# geiger2.net
KiCad netlist of a schematic drawn in EAGLE
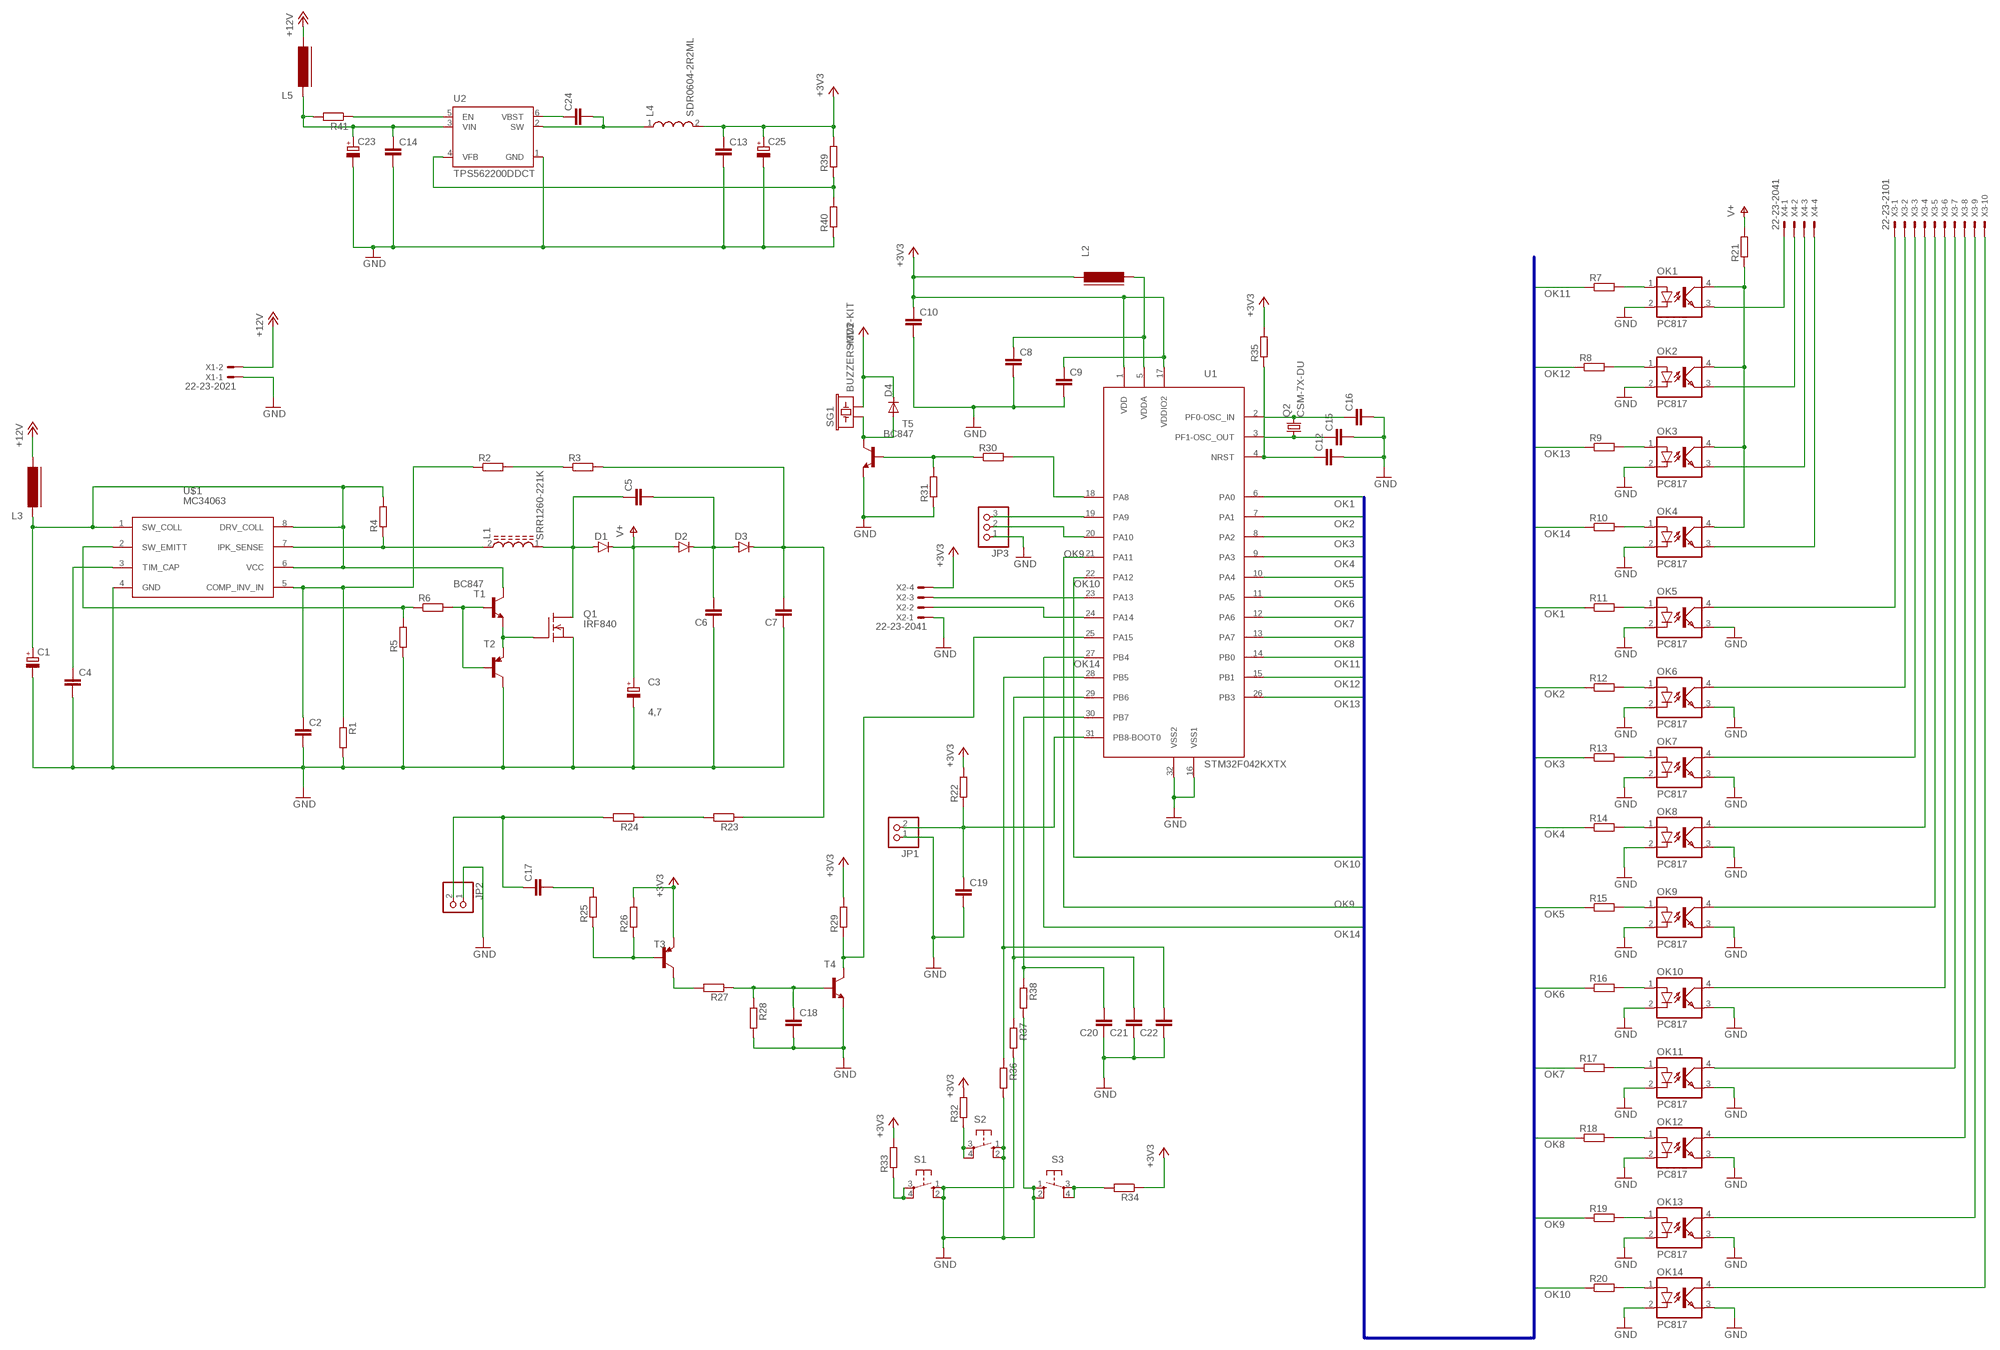
[diagram p0: schematic, sheet 1]

(export (version "E")
  (design (tool "Eeschema 10.0.6"))
  (components
    (comp (ref "C1")
      (value "CPOL-EUCT7343")
      (footprint "eagle-import:CT7343")
      (libsource (lib "eagle-import") (part "CPOL-EUCT7343"))
    )
    (comp (ref "C2")
      (value "C-EUC0805")
      (footprint "eagle-import:C0805")
      (libsource (lib "eagle-import") (part "rcl_334_C-EUC0805"))
    )
    (comp (ref "C3")
      (value "4,7")
      (footprint "eagle-import:E5-10,5")
      (libsource (lib "eagle-import") (part "rcl_334_CPOL-EUE5-10.5"))
    )
    (comp (ref "C4")
      (value "C-EUC0805")
      (footprint "eagle-import:C0805")
      (libsource (lib "eagle-import") (part "rcl_334_C-EUC0805"))
    )
    (comp (ref "C5")
      (value "C-EUC1812K")
      (footprint "eagle-import:C1812K")
      (libsource (lib "eagle-import") (part "C-EUC1812K"))
    )
    (comp (ref "C6")
      (value "C-EUC1812K")
      (footprint "eagle-import:C1812K")
      (libsource (lib "eagle-import") (part "C-EUC1812K"))
    )
    (comp (ref "C7")
      (value "C-EUC1812K")
      (footprint "eagle-import:C1812K")
      (libsource (lib "eagle-import") (part "C-EUC1812K"))
    )
    (comp (ref "C8")
      (value "C-EUC0805")
      (footprint "eagle-import:C0805")
      (libsource (lib "eagle-import") (part "rcl_334_C-EUC0805"))
    )
    (comp (ref "C9")
      (value "C-EUC0805")
      (footprint "eagle-import:C0805")
      (libsource (lib "eagle-import") (part "rcl_334_C-EUC0805"))
    )
    (comp (ref "C10")
      (value "C-EUC0805")
      (footprint "eagle-import:C0805")
      (libsource (lib "eagle-import") (part "rcl_334_C-EUC0805"))
    )
    (comp (ref "C12")
      (value "C-EUC0805")
      (footprint "eagle-import:C0805")
      (libsource (lib "eagle-import") (part "rcl_334_C-EUC0805"))
    )
    (comp (ref "C13")
      (value "C-EUC0805")
      (footprint "eagle-import:C0805")
      (libsource (lib "eagle-import") (part "rcl_334_C-EUC0805"))
    )
    (comp (ref "C14")
      (value "C-EUC0805")
      (footprint "eagle-import:C0805")
      (libsource (lib "eagle-import") (part "rcl_334_C-EUC0805"))
    )
    (comp (ref "C15")
      (value "C-EUC0805")
      (footprint "eagle-import:C0805")
      (libsource (lib "eagle-import") (part "rcl_334_C-EUC0805"))
    )
    (comp (ref "C16")
      (value "C-EUC0805")
      (footprint "eagle-import:C0805")
      (libsource (lib "eagle-import") (part "rcl_334_C-EUC0805"))
    )
    (comp (ref "C17")
      (value "C-EUC1206K")
      (footprint "eagle-import:C1206K")
      (libsource (lib "eagle-import") (part "rcl_334_C-EUC1206K"))
    )
    (comp (ref "C18")
      (value "C-EUC0805K")
      (footprint "eagle-import:C0805K")
      (libsource (lib "eagle-import") (part "rcl_334_C-EUC0805K"))
    )
    (comp (ref "C19")
      (value "C-EUC0805K")
      (footprint "eagle-import:C0805K")
      (libsource (lib "eagle-import") (part "rcl_334_C-EUC0805K"))
    )
    (comp (ref "C20")
      (value "C-EUC0805K")
      (footprint "eagle-import:C0805K")
      (libsource (lib "eagle-import") (part "rcl_334_C-EUC0805K"))
    )
    (comp (ref "C21")
      (value "C-EUC0805K")
      (footprint "eagle-import:C0805K")
      (libsource (lib "eagle-import") (part "rcl_334_C-EUC0805K"))
    )
    (comp (ref "C22")
      (value "C-EUC0805K")
      (footprint "eagle-import:C0805K")
      (libsource (lib "eagle-import") (part "rcl_334_C-EUC0805K"))
    )
    (comp (ref "C23")
      (value "CPOL-EUCT7343")
      (footprint "eagle-import:CT7343")
      (libsource (lib "eagle-import") (part "CPOL-EUCT7343"))
    )
    (comp (ref "C24")
      (value "C-EUC0805")
      (footprint "eagle-import:C0805")
      (libsource (lib "eagle-import") (part "rcl_334_C-EUC0805"))
    )
    (comp (ref "C25")
      (value "CPOL-EUCT7343")
      (footprint "eagle-import:CT7343")
      (libsource (lib "eagle-import") (part "CPOL-EUCT7343"))
    )
    (comp (ref "D1")
      (value "DIODE-DO214AC")
      (footprint "eagle-import:DO214AC")
      (libsource (lib "eagle-import") (part "DIODE-DO214AC"))
    )
    (comp (ref "D2")
      (value "DIODE-DO214AC")
      (footprint "eagle-import:DO214AC")
      (libsource (lib "eagle-import") (part "DIODE-DO214AC"))
    )
    (comp (ref "D3")
      (value "DIODE-DO214AC")
      (footprint "eagle-import:DO214AC")
      (libsource (lib "eagle-import") (part "DIODE-DO214AC"))
    )
    (comp (ref "D4")
      (value "DIODE-SOD-123")
      (footprint "eagle-import:SOD-123")
      (libsource (lib "eagle-import") (part "DIODE-SOD-123"))
    )
    (comp (ref "JP1")
      (value "PINHD-1X2")
      (footprint "eagle-import:1X02")
      (libsource (lib "eagle-import") (part "PINHD-1X2"))
    )
    (comp (ref "JP2")
      (value "PINHD-1X2")
      (footprint "eagle-import:1X02")
      (libsource (lib "eagle-import") (part "PINHD-1X2"))
    )
    (comp (ref "JP3")
      (value "PINHD-1X3")
      (footprint "eagle-import:1X03")
      (libsource (lib "eagle-import") (part "PINHD-1X3"))
    )
    (comp (ref "L1")
      (value "SRR1260-221K")
      (footprint "eagle-import:INDP125125X600N")
      (fields (field (name "MF") "Bourns - J.W. Miller"))
      (libsource (lib "eagle-import") (part "SRR1260-221K"))
    )
    (comp (ref "L2")
      (value "FERRITE-0805")
      (footprint "eagle-import:FB805")
      (libsource (lib "eagle-import") (part "FERRITE-0805"))
    )
    (comp (ref "L3")
      (value "FERRITE-0805")
      (footprint "eagle-import:FB805")
      (libsource (lib "eagle-import") (part "FERRITE-0805"))
    )
    (comp (ref "L4")
      (value "SDR0604-2R2ML")
      (footprint "eagle-import:INDP5858X480N")
      (fields (field (name "MF") "Bourns"))
      (libsource (lib "eagle-import") (part "SDR0604-2R2ML"))
    )
    (comp (ref "L5")
      (value "FERRITE-0805")
      (footprint "eagle-import:FB805")
      (libsource (lib "eagle-import") (part "FERRITE-0805"))
    )
    (comp (ref "OK1")
      (value "PC817")
      (footprint "eagle-import:DIL04")
      (fields (field (name "MPN") "PC817X4J000F"))
      (libsource (lib "eagle-import") (part "PC817"))
    )
    (comp (ref "OK2")
      (value "PC817")
      (footprint "eagle-import:DIL04")
      (fields (field (name "MPN") "PC817X4J000F"))
      (libsource (lib "eagle-import") (part "PC817"))
    )
    (comp (ref "OK3")
      (value "PC817")
      (footprint "eagle-import:DIL04")
      (fields (field (name "MPN") "PC817X4J000F"))
      (libsource (lib "eagle-import") (part "PC817"))
    )
    (comp (ref "OK4")
      (value "PC817")
      (footprint "eagle-import:DIL04")
      (fields (field (name "MPN") "PC817X4J000F"))
      (libsource (lib "eagle-import") (part "PC817"))
    )
    (comp (ref "OK5")
      (value "PC817")
      (footprint "eagle-import:DIL04")
      (fields (field (name "MPN") "PC817X4J000F"))
      (libsource (lib "eagle-import") (part "PC817"))
    )
    (comp (ref "OK6")
      (value "PC817")
      (footprint "eagle-import:DIL04")
      (fields (field (name "MPN") "PC817X4J000F"))
      (libsource (lib "eagle-import") (part "PC817"))
    )
    (comp (ref "OK7")
      (value "PC817")
      (footprint "eagle-import:DIL04")
      (fields (field (name "MPN") "PC817X4J000F"))
      (libsource (lib "eagle-import") (part "PC817"))
    )
    (comp (ref "OK8")
      (value "PC817")
      (footprint "eagle-import:DIL04")
      (fields (field (name "MPN") "PC817X4J000F"))
      (libsource (lib "eagle-import") (part "PC817"))
    )
    (comp (ref "OK9")
      (value "PC817")
      (footprint "eagle-import:DIL04")
      (fields (field (name "MPN") "PC817X4J000F"))
      (libsource (lib "eagle-import") (part "PC817"))
    )
    (comp (ref "OK10")
      (value "PC817")
      (footprint "eagle-import:DIL04")
      (fields (field (name "MPN") "PC817X4J000F"))
      (libsource (lib "eagle-import") (part "PC817"))
    )
    (comp (ref "OK11")
      (value "PC817")
      (footprint "eagle-import:DIL04")
      (fields (field (name "MPN") "PC817X4J000F"))
      (libsource (lib "eagle-import") (part "PC817"))
    )
    (comp (ref "OK12")
      (value "PC817")
      (footprint "eagle-import:DIL04")
      (fields (field (name "MPN") "PC817X4J000F"))
      (libsource (lib "eagle-import") (part "PC817"))
    )
    (comp (ref "OK13")
      (value "PC817")
      (footprint "eagle-import:DIL04")
      (fields (field (name "MPN") "PC817X4J000F"))
      (libsource (lib "eagle-import") (part "PC817"))
    )
    (comp (ref "OK14")
      (value "PC817")
      (footprint "eagle-import:DIL04")
      (fields (field (name "MPN") "PC817X4J000F"))
      (libsource (lib "eagle-import") (part "PC817"))
    )
    (comp (ref "Q1")
      (value "IRF840")
      (footprint "eagle-import:TO220")
      (libsource (lib "eagle-import") (part "IRF840"))
    )
    (comp (ref "Q2")
      (value "CSM-7X-DU")
      (footprint "eagle-import:CSM-7X-DU")
      (libsource (lib "eagle-import") (part "CSM-7X-DU"))
    )
    (comp (ref "R1")
      (value "R-EU_R0805")
      (footprint "eagle-import:R0805")
      (libsource (lib "eagle-import") (part "R-EU_R0805"))
    )
    (comp (ref "R2")
      (value "R-EU_R0805")
      (footprint "eagle-import:R0805")
      (libsource (lib "eagle-import") (part "R-EU_R0805"))
    )
    (comp (ref "R3")
      (value "R-EU_R0805")
      (footprint "eagle-import:R0805")
      (libsource (lib "eagle-import") (part "R-EU_R0805"))
    )
    (comp (ref "R4")
      (value "R-EU_R2512")
      (footprint "eagle-import:R2512")
      (libsource (lib "eagle-import") (part "R-EU_R2512"))
    )
    (comp (ref "R5")
      (value "R-EU_R0805")
      (footprint "eagle-import:R0805")
      (libsource (lib "eagle-import") (part "R-EU_R0805"))
    )
    (comp (ref "R6")
      (value "R-EU_R0805")
      (footprint "eagle-import:R0805")
      (libsource (lib "eagle-import") (part "R-EU_R0805"))
    )
    (comp (ref "R7")
      (value "R-EU_R0805")
      (footprint "eagle-import:R0805")
      (libsource (lib "eagle-import") (part "R-EU_R0805"))
    )
    (comp (ref "R8")
      (value "R-EU_R0805")
      (footprint "eagle-import:R0805")
      (libsource (lib "eagle-import") (part "R-EU_R0805"))
    )
    (comp (ref "R9")
      (value "R-EU_R0805")
      (footprint "eagle-import:R0805")
      (libsource (lib "eagle-import") (part "R-EU_R0805"))
    )
    (comp (ref "R10")
      (value "R-EU_R0805")
      (footprint "eagle-import:R0805")
      (libsource (lib "eagle-import") (part "R-EU_R0805"))
    )
    (comp (ref "R11")
      (value "R-EU_R0805")
      (footprint "eagle-import:R0805")
      (libsource (lib "eagle-import") (part "R-EU_R0805"))
    )
    (comp (ref "R12")
      (value "R-EU_R0805")
      (footprint "eagle-import:R0805")
      (libsource (lib "eagle-import") (part "R-EU_R0805"))
    )
    (comp (ref "R13")
      (value "R-EU_R0805")
      (footprint "eagle-import:R0805")
      (libsource (lib "eagle-import") (part "R-EU_R0805"))
    )
    (comp (ref "R14")
      (value "R-EU_R0805")
      (footprint "eagle-import:R0805")
      (libsource (lib "eagle-import") (part "R-EU_R0805"))
    )
    (comp (ref "R15")
      (value "R-EU_R0805")
      (footprint "eagle-import:R0805")
      (libsource (lib "eagle-import") (part "R-EU_R0805"))
    )
    (comp (ref "R16")
      (value "R-EU_R0805")
      (footprint "eagle-import:R0805")
      (libsource (lib "eagle-import") (part "R-EU_R0805"))
    )
    (comp (ref "R17")
      (value "R-EU_R0805")
      (footprint "eagle-import:R0805")
      (libsource (lib "eagle-import") (part "R-EU_R0805"))
    )
    (comp (ref "R18")
      (value "R-EU_R0805")
      (footprint "eagle-import:R0805")
      (libsource (lib "eagle-import") (part "R-EU_R0805"))
    )
    (comp (ref "R19")
      (value "R-EU_R0805")
      (footprint "eagle-import:R0805")
      (libsource (lib "eagle-import") (part "R-EU_R0805"))
    )
    (comp (ref "R20")
      (value "R-EU_R0805")
      (footprint "eagle-import:R0805")
      (libsource (lib "eagle-import") (part "R-EU_R0805"))
    )
    (comp (ref "R21")
      (value "R-EU_R1206")
      (footprint "eagle-import:R1206")
      (libsource (lib "eagle-import") (part "R-EU_R1206"))
    )
    (comp (ref "R22")
      (value "R-EU_R0805")
      (footprint "eagle-import:R0805")
      (libsource (lib "eagle-import") (part "R-EU_R0805"))
    )
    (comp (ref "R23")
      (value "R-EU_R1206")
      (footprint "eagle-import:R1206")
      (libsource (lib "eagle-import") (part "R-EU_R1206"))
    )
    (comp (ref "R24")
      (value "R-EU_R1206")
      (footprint "eagle-import:R1206")
      (libsource (lib "eagle-import") (part "R-EU_R1206"))
    )
    (comp (ref "R25")
      (value "R-EU_R0805")
      (footprint "eagle-import:R0805")
      (libsource (lib "eagle-import") (part "R-EU_R0805"))
    )
    (comp (ref "R26")
      (value "R-EU_R0805")
      (footprint "eagle-import:R0805")
      (libsource (lib "eagle-import") (part "R-EU_R0805"))
    )
    (comp (ref "R27")
      (value "R-EU_R0805")
      (footprint "eagle-import:R0805")
      (libsource (lib "eagle-import") (part "R-EU_R0805"))
    )
    (comp (ref "R28")
      (value "R-EU_R0805")
      (footprint "eagle-import:R0805")
      (libsource (lib "eagle-import") (part "R-EU_R0805"))
    )
    (comp (ref "R29")
      (value "R-EU_R0805")
      (footprint "eagle-import:R0805")
      (libsource (lib "eagle-import") (part "R-EU_R0805"))
    )
    (comp (ref "R30")
      (value "R-EU_R0805")
      (footprint "eagle-import:R0805")
      (libsource (lib "eagle-import") (part "R-EU_R0805"))
    )
    (comp (ref "R31")
      (value "R-EU_R0805")
      (footprint "eagle-import:R0805")
      (libsource (lib "eagle-import") (part "R-EU_R0805"))
    )
    (comp (ref "R32")
      (value "R-EU_R0805")
      (footprint "eagle-import:R0805")
      (libsource (lib "eagle-import") (part "R-EU_R0805"))
    )
    (comp (ref "R33")
      (value "R-EU_R0805")
      (footprint "eagle-import:R0805")
      (libsource (lib "eagle-import") (part "R-EU_R0805"))
    )
    (comp (ref "R34")
      (value "R-EU_R0805")
      (footprint "eagle-import:R0805")
      (libsource (lib "eagle-import") (part "R-EU_R0805"))
    )
    (comp (ref "R35")
      (value "R-EU_R0805")
      (footprint "eagle-import:R0805")
      (libsource (lib "eagle-import") (part "R-EU_R0805"))
    )
    (comp (ref "R36")
      (value "R-EU_R0805")
      (footprint "eagle-import:R0805")
      (libsource (lib "eagle-import") (part "R-EU_R0805"))
    )
    (comp (ref "R37")
      (value "R-EU_R0805")
      (footprint "eagle-import:R0805")
      (libsource (lib "eagle-import") (part "R-EU_R0805"))
    )
    (comp (ref "R38")
      (value "R-EU_R0805")
      (footprint "eagle-import:R0805")
      (libsource (lib "eagle-import") (part "R-EU_R0805"))
    )
    (comp (ref "R39")
      (value "R-EU_R0805")
      (footprint "eagle-import:R0805")
      (libsource (lib "eagle-import") (part "R-EU_R0805"))
    )
    (comp (ref "R40")
      (value "R-EU_R0805")
      (footprint "eagle-import:R0805")
      (libsource (lib "eagle-import") (part "R-EU_R0805"))
    )
    (comp (ref "R41")
      (value "R-EU_R0805")
      (footprint "eagle-import:R0805")
      (libsource (lib "eagle-import") (part "R-EU_R0805"))
    )
    (comp (ref "S1")
      (value "10-XX")
      (footprint "eagle-import:B3F-10XX")
      (fields (field (name "MPN") "B3F-1000"))
      (libsource (lib "eagle-import") (part "10-XX"))
    )
    (comp (ref "S2")
      (value "10-XX")
      (footprint "eagle-import:B3F-10XX")
      (fields (field (name "MPN") "B3F-1000"))
      (libsource (lib "eagle-import") (part "10-XX"))
    )
    (comp (ref "S3")
      (value "10-XX")
      (footprint "eagle-import:B3F-10XX")
      (fields (field (name "MPN") "B3F-1000"))
      (libsource (lib "eagle-import") (part "10-XX"))
    )
    (comp (ref "SG1")
      (value "BUZZERSMD2-KIT")
      (footprint "eagle-import:BUZZER-CCV-KIT")
      (libsource (lib "eagle-import") (part "BUZZERSMD2-KIT"))
    )
    (comp (ref "T1")
      (value "BC847")
      (footprint "eagle-import:SOT23")
      (libsource (lib "eagle-import") (part "BC847SMDBLT1"))
    )
    (comp (ref "T2")
      (value "BC857C-PNP-SOT23-BEC")
      (footprint "eagle-import:SOT23-BEC")
      (libsource (lib "eagle-import") (part "transistor-neu-to92_-PNP-SOT23-BECBC857C"))
    )
    (comp (ref "T3")
      (value "BC857A-PNP-SOT23-BEC")
      (footprint "eagle-import:SOT23-BEC")
      (libsource (lib "eagle-import") (part "-PNP-SOT23-BECBC857A"))
    )
    (comp (ref "T4")
      (value "BC847-NPN-SOT23-BEC")
      (footprint "eagle-import:SOT23-BEC")
      (libsource (lib "eagle-import") (part "-NPN-SOT23-BECBC847"))
    )
    (comp (ref "T5")
      (value "BC847")
      (footprint "eagle-import:SOT23")
      (libsource (lib "eagle-import") (part "BC847"))
    )
    (comp (ref "U$1")
      (value "MC34063")
      (footprint "eagle-import:SO-8")
      (libsource (lib "eagle-import") (part "MC34063/MC33063"))
    )
    (comp (ref "U1")
      (value "STM32F042KXTX")
      (footprint "eagle-import:LQFP32")
      (libsource (lib "eagle-import") (part "STM32F042KXTX"))
    )
    (comp (ref "U2")
      (value "TPS562200DDCT")
      (footprint "eagle-import:SOT95P280X110-6N")
      (fields (field (name "MF") "Texas Instruments"))
      (libsource (lib "eagle-import") (part "TPS562200DDCT"))
    )
    (comp (ref "X1")
      (value "22-23-2021")
      (footprint "eagle-import:22-23-2021")
      (fields (field (name "MF") "MOLEX"))
      (libsource (lib "eagle-import") (part "22-23-2021"))
    )
    (comp (ref "X2")
      (value "22-23-2041")
      (footprint "eagle-import:22-23-2041")
      (fields (field (name "MF") "MOLEX"))
      (libsource (lib "eagle-import") (part "22-23-2041"))
    )
    (comp (ref "X3")
      (value "22-23-2101")
      (footprint "eagle-import:22-23-2101")
      (fields (field (name "MF") "MOLEX"))
      (libsource (lib "eagle-import") (part "22-23-2101"))
    )
    (comp (ref "X4")
      (value "22-23-2041")
      (footprint "eagle-import:22-23-2041")
      (fields (field (name "MF") "MOLEX"))
      (libsource (lib "eagle-import") (part "22-23-2041"))
    )
  )
  (nets
    (net (code "1") (name "+3V3") (class "Default")
      (node (ref "C10") (pin "1") (pinfunction "1_1") (pintype "passive"))
      (node (ref "C13") (pin "1") (pinfunction "1_1") (pintype "passive"))
      (node (ref "C25") (pin "+") (pinfunction "+_+") (pintype "passive"))
      (node (ref "C9") (pin "1") (pinfunction "1_1") (pintype "passive"))
      (node (ref "D4") (pin "C") (pinfunction "C_C") (pintype "passive"))
      (node (ref "L2") (pin "1") (pinfunction "1_1") (pintype "passive"))
      (node (ref "L4") (pin "2") (pinfunction "2_2") (pintype "passive"))
      (node (ref "R22") (pin "2") (pinfunction "2_2") (pintype "passive"))
      (node (ref "R26") (pin "2") (pinfunction "2_2") (pintype "passive"))
      (node (ref "R29") (pin "2") (pinfunction "2_2") (pintype "passive"))
      (node (ref "R32") (pin "2") (pinfunction "2_2") (pintype "passive"))
      (node (ref "R33") (pin "2") (pinfunction "2_2") (pintype "passive"))
      (node (ref "R34") (pin "1") (pinfunction "1_1") (pintype "passive"))
      (node (ref "R35") (pin "2") (pinfunction "2_2") (pintype "passive"))
      (node (ref "R39") (pin "2") (pinfunction "2_2") (pintype "passive"))
      (node (ref "SG1") (pin "-") (pinfunction "2_-") (pintype "passive"))
      (node (ref "T3") (pin "E") (pinfunction "E_E") (pintype "passive"))
      (node (ref "U1") (pin "1") (pinfunction "VDD_1") (pintype "bidirectional"))
      (node (ref "U1") (pin "17") (pinfunction "VDDIO2_17") (pintype "bidirectional"))
      (node (ref "X2") (pin "4") (pinfunction "S_4") (pintype "passive"))
    )
    (net (code "2") (name "+12V") (class "Default")
      (node (ref "L3") (pin "2") (pinfunction "2_2") (pintype "passive"))
      (node (ref "L5") (pin "2") (pinfunction "2_2") (pintype "passive"))
      (node (ref "X1") (pin "2") (pinfunction "S_2") (pintype "passive"))
    )
    (net (code "3") (name "/OK1") (class "Default")
      (node (ref "R11") (pin "1") (pinfunction "1_1") (pintype "passive"))
      (node (ref "U1") (pin "6") (pinfunction "PA0_6") (pintype "bidirectional"))
    )
    (net (code "4") (name "/OK2") (class "Default")
      (node (ref "R12") (pin "1") (pinfunction "1_1") (pintype "passive"))
      (node (ref "U1") (pin "7") (pinfunction "PA1_7") (pintype "bidirectional"))
    )
    (net (code "5") (name "/OK3") (class "Default")
      (node (ref "R13") (pin "1") (pinfunction "1_1") (pintype "passive"))
      (node (ref "U1") (pin "8") (pinfunction "PA2_8") (pintype "bidirectional"))
    )
    (net (code "6") (name "/OK4") (class "Default")
      (node (ref "R14") (pin "1") (pinfunction "1_1") (pintype "passive"))
      (node (ref "U1") (pin "9") (pinfunction "PA3_9") (pintype "bidirectional"))
    )
    (net (code "7") (name "/OK5") (class "Default")
      (node (ref "R15") (pin "1") (pinfunction "1_1") (pintype "passive"))
      (node (ref "U1") (pin "10") (pinfunction "PA4_10") (pintype "bidirectional"))
    )
    (net (code "8") (name "/OK6") (class "Default")
      (node (ref "R16") (pin "1") (pinfunction "1_1") (pintype "passive"))
      (node (ref "U1") (pin "11") (pinfunction "PA5_11") (pintype "bidirectional"))
    )
    (net (code "9") (name "/OK7") (class "Default")
      (node (ref "R17") (pin "1") (pinfunction "1_1") (pintype "passive"))
      (node (ref "U1") (pin "12") (pinfunction "PA6_12") (pintype "bidirectional"))
    )
    (net (code "10") (name "/OK8") (class "Default")
      (node (ref "R18") (pin "1") (pinfunction "1_1") (pintype "passive"))
      (node (ref "U1") (pin "13") (pinfunction "PA7_13") (pintype "bidirectional"))
    )
    (net (code "11") (name "/OK9") (class "Default")
      (node (ref "R19") (pin "1") (pinfunction "1_1") (pintype "passive"))
      (node (ref "U1") (pin "21") (pinfunction "PA11_21") (pintype "bidirectional"))
    )
    (net (code "12") (name "/OK10") (class "Default")
      (node (ref "R20") (pin "1") (pinfunction "1_1") (pintype "passive"))
      (node (ref "U1") (pin "22") (pinfunction "PA12_22") (pintype "bidirectional"))
    )
    (net (code "13") (name "/OK11") (class "Default")
      (node (ref "R7") (pin "1") (pinfunction "1_1") (pintype "passive"))
      (node (ref "U1") (pin "14") (pinfunction "PB0_14") (pintype "bidirectional"))
    )
    (net (code "14") (name "/OK12") (class "Default")
      (node (ref "R8") (pin "1") (pinfunction "1_1") (pintype "passive"))
      (node (ref "U1") (pin "15") (pinfunction "PB1_15") (pintype "bidirectional"))
    )
    (net (code "15") (name "/OK13") (class "Default")
      (node (ref "R9") (pin "1") (pinfunction "1_1") (pintype "passive"))
      (node (ref "U1") (pin "26") (pinfunction "PB3_26") (pintype "bidirectional"))
    )
    (net (code "16") (name "/OK14") (class "Default")
      (node (ref "R10") (pin "1") (pinfunction "1_1") (pintype "passive"))
      (node (ref "U1") (pin "27") (pinfunction "PB4_27") (pintype "bidirectional"))
    )
    (net (code "17") (name "GND") (class "Default")
      (node (ref "C1") (pin "-") (pinfunction "-_-") (pintype "passive"))
      (node (ref "C10") (pin "2") (pinfunction "2_2") (pintype "passive"))
      (node (ref "C12") (pin "2") (pinfunction "2_2") (pintype "passive"))
      (node (ref "C13") (pin "2") (pinfunction "2_2") (pintype "passive"))
      (node (ref "C14") (pin "2") (pinfunction "2_2") (pintype "passive"))
      (node (ref "C15") (pin "2") (pinfunction "2_2") (pintype "passive"))
      (node (ref "C16") (pin "2") (pinfunction "2_2") (pintype "passive"))
      (node (ref "C18") (pin "2") (pinfunction "2_2") (pintype "passive"))
      (node (ref "C19") (pin "2") (pinfunction "2_2") (pintype "passive"))
      (node (ref "C2") (pin "2") (pinfunction "2_2") (pintype "passive"))
      (node (ref "C20") (pin "1") (pinfunction "1_1") (pintype "passive"))
      (node (ref "C21") (pin "1") (pinfunction "1_1") (pintype "passive"))
      (node (ref "C22") (pin "1") (pinfunction "1_1") (pintype "passive"))
      (node (ref "C23") (pin "-") (pinfunction "-_-") (pintype "passive"))
      (node (ref "C25") (pin "-") (pinfunction "-_-") (pintype "passive"))
      (node (ref "C3") (pin "-") (pinfunction "-_-") (pintype "passive"))
      (node (ref "C4") (pin "2") (pinfunction "2_2") (pintype "passive"))
      (node (ref "C6") (pin "1") (pinfunction "1_1") (pintype "passive"))
      (node (ref "C7") (pin "1") (pinfunction "1_1") (pintype "passive"))
      (node (ref "C8") (pin "2") (pinfunction "2_2") (pintype "passive"))
      (node (ref "C9") (pin "2") (pinfunction "2_2") (pintype "passive"))
      (node (ref "JP1") (pin "1") (pinfunction "1_1") (pintype "passive"))
      (node (ref "JP2") (pin "1") (pinfunction "1_1") (pintype "passive"))
      (node (ref "JP3") (pin "1") (pinfunction "1_1") (pintype "passive"))
      (node (ref "OK1") (pin "2") (pinfunction "C_2") (pintype "passive"))
      (node (ref "OK10") (pin "2") (pinfunction "C_2") (pintype "passive"))
      (node (ref "OK10") (pin "3") (pinfunction "EMIT_3") (pintype "passive"))
      (node (ref "OK11") (pin "2") (pinfunction "C_2") (pintype "passive"))
      (node (ref "OK11") (pin "3") (pinfunction "EMIT_3") (pintype "passive"))
      (node (ref "OK12") (pin "2") (pinfunction "C_2") (pintype "passive"))
      (node (ref "OK12") (pin "3") (pinfunction "EMIT_3") (pintype "passive"))
      (node (ref "OK13") (pin "2") (pinfunction "C_2") (pintype "passive"))
      (node (ref "OK13") (pin "3") (pinfunction "EMIT_3") (pintype "passive"))
      (node (ref "OK14") (pin "2") (pinfunction "C_2") (pintype "passive"))
      (node (ref "OK14") (pin "3") (pinfunction "EMIT_3") (pintype "passive"))
      (node (ref "OK2") (pin "2") (pinfunction "C_2") (pintype "passive"))
      (node (ref "OK3") (pin "2") (pinfunction "C_2") (pintype "passive"))
      (node (ref "OK4") (pin "2") (pinfunction "C_2") (pintype "passive"))
      (node (ref "OK5") (pin "2") (pinfunction "C_2") (pintype "passive"))
      (node (ref "OK5") (pin "3") (pinfunction "EMIT_3") (pintype "passive"))
      (node (ref "OK6") (pin "2") (pinfunction "C_2") (pintype "passive"))
      (node (ref "OK6") (pin "3") (pinfunction "EMIT_3") (pintype "passive"))
      (node (ref "OK7") (pin "2") (pinfunction "C_2") (pintype "passive"))
      (node (ref "OK7") (pin "3") (pinfunction "EMIT_3") (pintype "passive"))
      (node (ref "OK8") (pin "2") (pinfunction "C_2") (pintype "passive"))
      (node (ref "OK8") (pin "3") (pinfunction "EMIT_3") (pintype "passive"))
      (node (ref "OK9") (pin "2") (pinfunction "C_2") (pintype "passive"))
      (node (ref "OK9") (pin "3") (pinfunction "EMIT_3") (pintype "passive"))
      (node (ref "Q1") (pin "3") (pinfunction "S_3") (pintype "passive"))
      (node (ref "R1") (pin "2") (pinfunction "2_2") (pintype "passive"))
      (node (ref "R28") (pin "2") (pinfunction "2_2") (pintype "passive"))
      (node (ref "R31") (pin "1") (pinfunction "1_1") (pintype "passive"))
      (node (ref "R36") (pin "2") (pinfunction "2_2") (pintype "passive"))
      (node (ref "R37") (pin "2") (pinfunction "2_2") (pintype "passive"))
      (node (ref "R38") (pin "2") (pinfunction "2_2") (pintype "passive"))
      (node (ref "R40") (pin "1") (pinfunction "1_1") (pintype "passive"))
      (node (ref "R5") (pin "1") (pinfunction "1_1") (pintype "passive"))
      (node (ref "S1") (pin "1") (pinfunction "S_1") (pintype "passive"))
      (node (ref "S1") (pin "2") (pinfunction "S1_2") (pintype "passive"))
      (node (ref "S2") (pin "1") (pinfunction "S_1") (pintype "passive"))
      (node (ref "S2") (pin "2") (pinfunction "S1_2") (pintype "passive"))
      (node (ref "S3") (pin "1") (pinfunction "S_1") (pintype "passive"))
      (node (ref "S3") (pin "2") (pinfunction "S1_2") (pintype "passive"))
      (node (ref "T2") (pin "C") (pinfunction "C_C") (pintype "passive"))
      (node (ref "T4") (pin "E") (pinfunction "E_E") (pintype "passive"))
      (node (ref "T5") (pin "2") (pinfunction "E_2") (pintype "passive"))
      (node (ref "U$1") (pin "4") (pinfunction "GND_4") (pintype "bidirectional"))
      (node (ref "U1") (pin "16") (pinfunction "VSS1_16") (pintype "bidirectional"))
      (node (ref "U1") (pin "32") (pinfunction "VSS2_32") (pintype "bidirectional"))
      (node (ref "U2") (pin "1") (pinfunction "GND_1") (pintype "power_in"))
      (node (ref "X1") (pin "1") (pinfunction "S_1") (pintype "passive"))
      (node (ref "X2") (pin "1") (pinfunction "S_1") (pintype "passive"))
    )
    (net (code "18") (name "Net-(C5-Pad2)") (class "Default")
      (node (ref "C5") (pin "2") (pinfunction "2_2") (pintype "passive"))
      (node (ref "C6") (pin "2") (pinfunction "2_2") (pintype "passive"))
      (node (ref "D2") (pin "C") (pinfunction "C_C") (pintype "passive"))
      (node (ref "D3") (pin "A") (pinfunction "A_A") (pintype "passive"))
    )
    (net (code "19") (name "Net-(C7-Pad2)") (class "Default")
      (node (ref "C7") (pin "2") (pinfunction "2_2") (pintype "passive"))
      (node (ref "D3") (pin "C") (pinfunction "C_C") (pintype "passive"))
      (node (ref "R23") (pin "1") (pinfunction "1_1") (pintype "passive"))
      (node (ref "R3") (pin "2") (pinfunction "2_2") (pintype "passive"))
    )
    (net (code "20") (name "Net-(C17-Pad1)") (class "Default")
      (node (ref "C17") (pin "1") (pinfunction "1_1") (pintype "passive"))
      (node (ref "JP2") (pin "2") (pinfunction "2_2") (pintype "passive"))
      (node (ref "R24") (pin "2") (pinfunction "2_2") (pintype "passive"))
    )
    (net (code "21") (name "Net-(C17-Pad2)") (class "Default")
      (node (ref "C17") (pin "2") (pinfunction "2_2") (pintype "passive"))
      (node (ref "R25") (pin "2") (pinfunction "2_2") (pintype "passive"))
    )
    (net (code "22") (name "Net-(C18-Pad1)") (class "Default")
      (node (ref "C18") (pin "1") (pinfunction "1_1") (pintype "passive"))
      (node (ref "R27") (pin "1") (pinfunction "1_1") (pintype "passive"))
      (node (ref "R28") (pin "1") (pinfunction "1_1") (pintype "passive"))
      (node (ref "T4") (pin "B") (pinfunction "B_B") (pintype "passive"))
    )
    (net (code "23") (name "Net-(OK1-A)") (class "Default")
      (node (ref "OK1") (pin "1") (pinfunction "A_1") (pintype "passive"))
      (node (ref "R7") (pin "2") (pinfunction "2_2") (pintype "passive"))
    )
    (net (code "24") (name "Net-(OK1-COL)") (class "Default")
      (node (ref "OK1") (pin "4") (pinfunction "COL_4") (pintype "passive"))
      (node (ref "OK2") (pin "4") (pinfunction "COL_4") (pintype "passive"))
      (node (ref "OK3") (pin "4") (pinfunction "COL_4") (pintype "passive"))
      (node (ref "OK4") (pin "4") (pinfunction "COL_4") (pintype "passive"))
      (node (ref "R21") (pin "1") (pinfunction "1_1") (pintype "passive"))
    )
    (net (code "25") (name "Net-(OK1-EMIT)") (class "Default")
      (node (ref "OK1") (pin "3") (pinfunction "EMIT_3") (pintype "passive"))
      (node (ref "X4") (pin "1") (pinfunction "S_1") (pintype "passive"))
    )
    (net (code "26") (name "Net-(OK2-A)") (class "Default")
      (node (ref "OK2") (pin "1") (pinfunction "A_1") (pintype "passive"))
      (node (ref "R8") (pin "2") (pinfunction "2_2") (pintype "passive"))
    )
    (net (code "27") (name "Net-(OK2-EMIT)") (class "Default")
      (node (ref "OK2") (pin "3") (pinfunction "EMIT_3") (pintype "passive"))
      (node (ref "X4") (pin "2") (pinfunction "S_2") (pintype "passive"))
    )
    (net (code "28") (name "Net-(OK3-A)") (class "Default")
      (node (ref "OK3") (pin "1") (pinfunction "A_1") (pintype "passive"))
      (node (ref "R9") (pin "2") (pinfunction "2_2") (pintype "passive"))
    )
    (net (code "29") (name "Net-(OK3-EMIT)") (class "Default")
      (node (ref "OK3") (pin "3") (pinfunction "EMIT_3") (pintype "passive"))
      (node (ref "X4") (pin "3") (pinfunction "S_3") (pintype "passive"))
    )
    (net (code "30") (name "Net-(OK4-A)") (class "Default")
      (node (ref "OK4") (pin "1") (pinfunction "A_1") (pintype "passive"))
      (node (ref "R10") (pin "2") (pinfunction "2_2") (pintype "passive"))
    )
    (net (code "31") (name "Net-(OK4-EMIT)") (class "Default")
      (node (ref "OK4") (pin "3") (pinfunction "EMIT_3") (pintype "passive"))
      (node (ref "X4") (pin "4") (pinfunction "S_4") (pintype "passive"))
    )
    (net (code "32") (name "Net-(OK5-A)") (class "Default")
      (node (ref "OK5") (pin "1") (pinfunction "A_1") (pintype "passive"))
      (node (ref "R11") (pin "2") (pinfunction "2_2") (pintype "passive"))
    )
    (net (code "33") (name "Net-(OK5-COL)") (class "Default")
      (node (ref "OK5") (pin "4") (pinfunction "COL_4") (pintype "passive"))
      (node (ref "X3") (pin "1") (pinfunction "S_1") (pintype "passive"))
    )
    (net (code "34") (name "Net-(OK6-A)") (class "Default")
      (node (ref "OK6") (pin "1") (pinfunction "A_1") (pintype "passive"))
      (node (ref "R12") (pin "2") (pinfunction "2_2") (pintype "passive"))
    )
    (net (code "35") (name "Net-(OK6-COL)") (class "Default")
      (node (ref "OK6") (pin "4") (pinfunction "COL_4") (pintype "passive"))
      (node (ref "X3") (pin "2") (pinfunction "S_2") (pintype "passive"))
    )
    (net (code "36") (name "Net-(OK7-A)") (class "Default")
      (node (ref "OK7") (pin "1") (pinfunction "A_1") (pintype "passive"))
      (node (ref "R13") (pin "2") (pinfunction "2_2") (pintype "passive"))
    )
    (net (code "37") (name "Net-(OK7-COL)") (class "Default")
      (node (ref "OK7") (pin "4") (pinfunction "COL_4") (pintype "passive"))
      (node (ref "X3") (pin "3") (pinfunction "S_3") (pintype "passive"))
    )
    (net (code "38") (name "Net-(OK8-A)") (class "Default")
      (node (ref "OK8") (pin "1") (pinfunction "A_1") (pintype "passive"))
      (node (ref "R14") (pin "2") (pinfunction "2_2") (pintype "passive"))
    )
    (net (code "39") (name "Net-(OK8-COL)") (class "Default")
      (node (ref "OK8") (pin "4") (pinfunction "COL_4") (pintype "passive"))
      (node (ref "X3") (pin "4") (pinfunction "S_4") (pintype "passive"))
    )
    (net (code "40") (name "Net-(OK9-A)") (class "Default")
      (node (ref "OK9") (pin "1") (pinfunction "A_1") (pintype "passive"))
      (node (ref "R15") (pin "2") (pinfunction "2_2") (pintype "passive"))
    )
    (net (code "41") (name "Net-(OK9-COL)") (class "Default")
      (node (ref "OK9") (pin "4") (pinfunction "COL_4") (pintype "passive"))
      (node (ref "X3") (pin "5") (pinfunction "S_5") (pintype "passive"))
    )
    (net (code "42") (name "Net-(OK10-A)") (class "Default")
      (node (ref "OK10") (pin "1") (pinfunction "A_1") (pintype "passive"))
      (node (ref "R16") (pin "2") (pinfunction "2_2") (pintype "passive"))
    )
    (net (code "43") (name "Net-(OK10-COL)") (class "Default")
      (node (ref "OK10") (pin "4") (pinfunction "COL_4") (pintype "passive"))
      (node (ref "X3") (pin "6") (pinfunction "S_6") (pintype "passive"))
    )
    (net (code "44") (name "Net-(OK11-A)") (class "Default")
      (node (ref "OK11") (pin "1") (pinfunction "A_1") (pintype "passive"))
      (node (ref "R17") (pin "2") (pinfunction "2_2") (pintype "passive"))
    )
    (net (code "45") (name "Net-(OK11-COL)") (class "Default")
      (node (ref "OK11") (pin "4") (pinfunction "COL_4") (pintype "passive"))
      (node (ref "X3") (pin "7") (pinfunction "S_7") (pintype "passive"))
    )
    (net (code "46") (name "Net-(OK12-A)") (class "Default")
      (node (ref "OK12") (pin "1") (pinfunction "A_1") (pintype "passive"))
      (node (ref "R18") (pin "2") (pinfunction "2_2") (pintype "passive"))
    )
    (net (code "47") (name "Net-(OK12-COL)") (class "Default")
      (node (ref "OK12") (pin "4") (pinfunction "COL_4") (pintype "passive"))
      (node (ref "X3") (pin "8") (pinfunction "S_8") (pintype "passive"))
    )
    (net (code "48") (name "Net-(OK13-A)") (class "Default")
      (node (ref "OK13") (pin "1") (pinfunction "A_1") (pintype "passive"))
      (node (ref "R19") (pin "2") (pinfunction "2_2") (pintype "passive"))
    )
    (net (code "49") (name "Net-(OK13-COL)") (class "Default")
      (node (ref "OK13") (pin "4") (pinfunction "COL_4") (pintype "passive"))
      (node (ref "X3") (pin "9") (pinfunction "S_9") (pintype "passive"))
    )
    (net (code "50") (name "Net-(OK14-A)") (class "Default")
      (node (ref "OK14") (pin "1") (pinfunction "A_1") (pintype "passive"))
      (node (ref "R20") (pin "2") (pinfunction "2_2") (pintype "passive"))
    )
    (net (code "51") (name "Net-(OK14-COL)") (class "Default")
      (node (ref "OK14") (pin "4") (pinfunction "COL_4") (pintype "passive"))
      (node (ref "X3") (pin "10") (pinfunction "S_10") (pintype "passive"))
    )
    (net (code "52") (name "Net-(Q1-D)") (class "Default")
      (node (ref "C5") (pin "1") (pinfunction "1_1") (pintype "passive"))
      (node (ref "D1") (pin "A") (pinfunction "A_A") (pintype "passive"))
      (node (ref "L1") (pin "1") (pinfunction "1_1") (pintype "passive"))
      (node (ref "Q1") (pin "2") (pinfunction "D_2") (pintype "passive"))
    )
    (net (code "53") (name "Net-(Q1-G)") (class "Default")
      (node (ref "Q1") (pin "1") (pinfunction "G_1") (pintype "passive"))
      (node (ref "T1") (pin "2") (pinfunction "E_2") (pintype "passive"))
      (node (ref "T2") (pin "E") (pinfunction "E_E") (pintype "passive"))
    )
    (net (code "54") (name "Net-(R2-Pad2)") (class "Default")
      (node (ref "R2") (pin "2") (pinfunction "2_2") (pintype "passive"))
      (node (ref "R3") (pin "1") (pinfunction "1_1") (pintype "passive"))
    )
    (net (code "55") (name "Net-(R23-Pad2)") (class "Default")
      (node (ref "R23") (pin "2") (pinfunction "2_2") (pintype "passive"))
      (node (ref "R24") (pin "1") (pinfunction "1_1") (pintype "passive"))
    )
    (net (code "56") (name "Net-(R25-Pad1)") (class "Default")
      (node (ref "R25") (pin "1") (pinfunction "1_1") (pintype "passive"))
      (node (ref "R26") (pin "1") (pinfunction "1_1") (pintype "passive"))
      (node (ref "T3") (pin "B") (pinfunction "B_B") (pintype "passive"))
    )
    (net (code "57") (name "Net-(R27-Pad2)") (class "Default")
      (node (ref "R27") (pin "2") (pinfunction "2_2") (pintype "passive"))
      (node (ref "T3") (pin "C") (pinfunction "C_C") (pintype "passive"))
    )
    (net (code "58") (name "Net-(S1-P)") (class "Default")
      (node (ref "R33") (pin "1") (pinfunction "1_1") (pintype "passive"))
      (node (ref "S1") (pin "3") (pinfunction "P_3") (pintype "passive"))
      (node (ref "S1") (pin "4") (pinfunction "P1_4") (pintype "passive"))
    )
    (net (code "59") (name "Net-(S2-P)") (class "Default")
      (node (ref "R32") (pin "1") (pinfunction "1_1") (pintype "passive"))
      (node (ref "S2") (pin "3") (pinfunction "P_3") (pintype "passive"))
      (node (ref "S2") (pin "4") (pinfunction "P1_4") (pintype "passive"))
    )
    (net (code "60") (name "Net-(S3-P)") (class "Default")
      (node (ref "R34") (pin "2") (pinfunction "2_2") (pintype "passive"))
      (node (ref "S3") (pin "3") (pinfunction "P_3") (pintype "passive"))
      (node (ref "S3") (pin "4") (pinfunction "P1_4") (pintype "passive"))
    )
    (net (code "61") (name "Net-(SG1-1)") (class "Default")
      (node (ref "D4") (pin "A") (pinfunction "A_A") (pintype "passive"))
      (node (ref "SG1") (pin "+") (pinfunction "1_+") (pintype "passive"))
      (node (ref "T5") (pin "3") (pinfunction "C_3") (pintype "passive"))
    )
    (net (code "62") (name "Net-(T1-B)") (class "Default")
      (node (ref "R6") (pin "2") (pinfunction "2_2") (pintype "passive"))
      (node (ref "T1") (pin "1") (pinfunction "B_1") (pintype "passive"))
      (node (ref "T2") (pin "B") (pinfunction "B_B") (pintype "passive"))
    )
    (net (code "63") (name "Net-(T1-C)") (class "Default")
      (node (ref "C1") (pin "+") (pinfunction "+_+") (pintype "passive"))
      (node (ref "L3") (pin "1") (pinfunction "1_1") (pintype "passive"))
      (node (ref "R4") (pin "2") (pinfunction "2_2") (pintype "passive"))
      (node (ref "T1") (pin "3") (pinfunction "C_3") (pintype "passive"))
      (node (ref "U$1") (pin "1") (pinfunction "SW_COLL_1") (pintype "bidirectional"))
      (node (ref "U$1") (pin "6") (pinfunction "VCC_6") (pintype "bidirectional"))
      (node (ref "U$1") (pin "8") (pinfunction "DRV_COLL_8") (pintype "bidirectional"))
    )
    (net (code "64") (name "Net-(T5-B)") (class "Default")
      (node (ref "R30") (pin "1") (pinfunction "1_1") (pintype "passive"))
      (node (ref "R31") (pin "2") (pinfunction "2_2") (pintype "passive"))
      (node (ref "T5") (pin "1") (pinfunction "B_1") (pintype "passive"))
    )
    (net (code "65") (name "Net-(U$1-COMP_INV_IN)") (class "Default")
      (node (ref "C2") (pin "1") (pinfunction "1_1") (pintype "passive"))
      (node (ref "R1") (pin "1") (pinfunction "1_1") (pintype "passive"))
      (node (ref "R2") (pin "1") (pinfunction "1_1") (pintype "passive"))
      (node (ref "U$1") (pin "5") (pinfunction "COMP_INV_IN_5") (pintype "bidirectional"))
    )
    (net (code "66") (name "Net-(U$1-IPK_SENSE)") (class "Default")
      (node (ref "L1") (pin "2") (pinfunction "2_2") (pintype "passive"))
      (node (ref "R4") (pin "1") (pinfunction "1_1") (pintype "passive"))
      (node (ref "U$1") (pin "7") (pinfunction "IPK_SENSE_7") (pintype "bidirectional"))
    )
    (net (code "67") (name "Net-(U$1-SW_EMITT)") (class "Default")
      (node (ref "R5") (pin "2") (pinfunction "2_2") (pintype "passive"))
      (node (ref "R6") (pin "1") (pinfunction "1_1") (pintype "passive"))
      (node (ref "U$1") (pin "2") (pinfunction "SW_EMITT_2") (pintype "bidirectional"))
    )
    (net (code "68") (name "Net-(U$1-TIM_CAP)") (class "Default")
      (node (ref "C4") (pin "1") (pinfunction "1_1") (pintype "passive"))
      (node (ref "U$1") (pin "3") (pinfunction "TIM_CAP_3") (pintype "bidirectional"))
    )
    (net (code "69") (name "Net-(U1-NRST)") (class "Default")
      (node (ref "C12") (pin "1") (pinfunction "1_1") (pintype "passive"))
      (node (ref "R35") (pin "1") (pinfunction "1_1") (pintype "passive"))
      (node (ref "U1") (pin "4") (pinfunction "NRST_4") (pintype "bidirectional"))
    )
    (net (code "70") (name "Net-(U1-PA8)") (class "Default")
      (node (ref "R30") (pin "2") (pinfunction "2_2") (pintype "passive"))
      (node (ref "U1") (pin "18") (pinfunction "PA8_18") (pintype "bidirectional"))
    )
    (net (code "71") (name "Net-(U1-PA9)") (class "Default")
      (node (ref "JP3") (pin "3") (pinfunction "3_3") (pintype "passive"))
      (node (ref "U1") (pin "19") (pinfunction "PA9_19") (pintype "bidirectional"))
    )
    (net (code "72") (name "Net-(U1-PA10)") (class "Default")
      (node (ref "JP3") (pin "2") (pinfunction "2_2") (pintype "passive"))
      (node (ref "U1") (pin "20") (pinfunction "PA10_20") (pintype "bidirectional"))
    )
    (net (code "73") (name "Net-(U1-PA13)") (class "Default")
      (node (ref "U1") (pin "23") (pinfunction "PA13_23") (pintype "bidirectional"))
      (node (ref "X2") (pin "3") (pinfunction "S_3") (pintype "passive"))
    )
    (net (code "74") (name "Net-(U1-PA14)") (class "Default")
      (node (ref "U1") (pin "24") (pinfunction "PA14_24") (pintype "bidirectional"))
      (node (ref "X2") (pin "2") (pinfunction "S_2") (pintype "passive"))
    )
    (net (code "75") (name "Net-(U1-PA15)") (class "Default")
      (node (ref "R29") (pin "1") (pinfunction "1_1") (pintype "passive"))
      (node (ref "T4") (pin "C") (pinfunction "C_C") (pintype "passive"))
      (node (ref "U1") (pin "25") (pinfunction "PA15_25") (pintype "bidirectional"))
    )
    (net (code "76") (name "Net-(U1-PB5)") (class "Default")
      (node (ref "C22") (pin "2") (pinfunction "2_2") (pintype "passive"))
      (node (ref "R36") (pin "1") (pinfunction "1_1") (pintype "passive"))
      (node (ref "U1") (pin "28") (pinfunction "PB5_28") (pintype "bidirectional"))
    )
    (net (code "77") (name "Net-(U1-PB6)") (class "Default")
      (node (ref "C21") (pin "2") (pinfunction "2_2") (pintype "passive"))
      (node (ref "R37") (pin "1") (pinfunction "1_1") (pintype "passive"))
      (node (ref "U1") (pin "29") (pinfunction "PB6_29") (pintype "bidirectional"))
    )
    (net (code "78") (name "Net-(U1-PB7)") (class "Default")
      (node (ref "C20") (pin "2") (pinfunction "2_2") (pintype "passive"))
      (node (ref "R38") (pin "1") (pinfunction "1_1") (pintype "passive"))
      (node (ref "U1") (pin "30") (pinfunction "PB7_30") (pintype "bidirectional"))
    )
    (net (code "79") (name "Net-(U1-PB8-BOOT0)") (class "Default")
      (node (ref "C19") (pin "1") (pinfunction "1_1") (pintype "passive"))
      (node (ref "JP1") (pin "2") (pinfunction "2_2") (pintype "passive"))
      (node (ref "R22") (pin "1") (pinfunction "1_1") (pintype "passive"))
      (node (ref "U1") (pin "31") (pinfunction "PB8-BOOT0_31") (pintype "bidirectional"))
    )
    (net (code "80") (name "Net-(U1-PF0-OSC_IN)") (class "Default")
      (node (ref "C16") (pin "1") (pinfunction "1_1") (pintype "passive"))
      (node (ref "Q2") (pin "2") (pinfunction "2_2") (pintype "passive"))
      (node (ref "U1") (pin "2") (pinfunction "PF0-OSC_IN_2") (pintype "bidirectional"))
    )
    (net (code "81") (name "Net-(U1-PF1-OSC_OUT)") (class "Default")
      (node (ref "C15") (pin "1") (pinfunction "1_1") (pintype "passive"))
      (node (ref "Q2") (pin "1") (pinfunction "1_1") (pintype "passive"))
      (node (ref "U1") (pin "3") (pinfunction "PF1-OSC_OUT_3") (pintype "bidirectional"))
    )
    (net (code "82") (name "Net-(U1-VDDA)") (class "Default")
      (node (ref "C8") (pin "1") (pinfunction "1_1") (pintype "passive"))
      (node (ref "L2") (pin "2") (pinfunction "2_2") (pintype "passive"))
      (node (ref "U1") (pin "5") (pinfunction "VDDA_5") (pintype "bidirectional"))
    )
    (net (code "83") (name "Net-(U2-EN)") (class "Default")
      (node (ref "R41") (pin "1") (pinfunction "1_1") (pintype "passive"))
      (node (ref "U2") (pin "5") (pinfunction "EN_5") (pintype "input"))
    )
    (net (code "84") (name "Net-(U2-SW)") (class "Default")
      (node (ref "C24") (pin "2") (pinfunction "2_2") (pintype "passive"))
      (node (ref "L4") (pin "1") (pinfunction "1_1") (pintype "passive"))
      (node (ref "U2") (pin "2") (pinfunction "SW_2") (pintype "output"))
    )
    (net (code "85") (name "Net-(U2-VBST)") (class "Default")
      (node (ref "C24") (pin "1") (pinfunction "1_1") (pintype "passive"))
      (node (ref "U2") (pin "6") (pinfunction "VBST_6") (pintype "power_in"))
    )
    (net (code "86") (name "Net-(U2-VFB)") (class "Default")
      (node (ref "R39") (pin "1") (pinfunction "1_1") (pintype "passive"))
      (node (ref "R40") (pin "2") (pinfunction "2_2") (pintype "passive"))
      (node (ref "U2") (pin "4") (pinfunction "VFB_4") (pintype "input"))
    )
    (net (code "87") (name "Net-(U2-VIN)") (class "Default")
      (node (ref "C14") (pin "1") (pinfunction "1_1") (pintype "passive"))
      (node (ref "C23") (pin "+") (pinfunction "+_+") (pintype "passive"))
      (node (ref "L5") (pin "1") (pinfunction "1_1") (pintype "passive"))
      (node (ref "R41") (pin "2") (pinfunction "2_2") (pintype "passive"))
      (node (ref "U2") (pin "3") (pinfunction "VIN_3") (pintype "input"))
    )
    (net (code "88") (name "V+") (class "Default")
      (node (ref "C3") (pin "+") (pinfunction "+_+") (pintype "passive"))
      (node (ref "D1") (pin "C") (pinfunction "C_C") (pintype "passive"))
      (node (ref "D2") (pin "A") (pinfunction "A_A") (pintype "passive"))
      (node (ref "R21") (pin "2") (pinfunction "2_2") (pintype "passive"))
    )
  )
)
